# Zuino_M_UNO.net
KiCad netlist of a schematic drawn in EAGLE
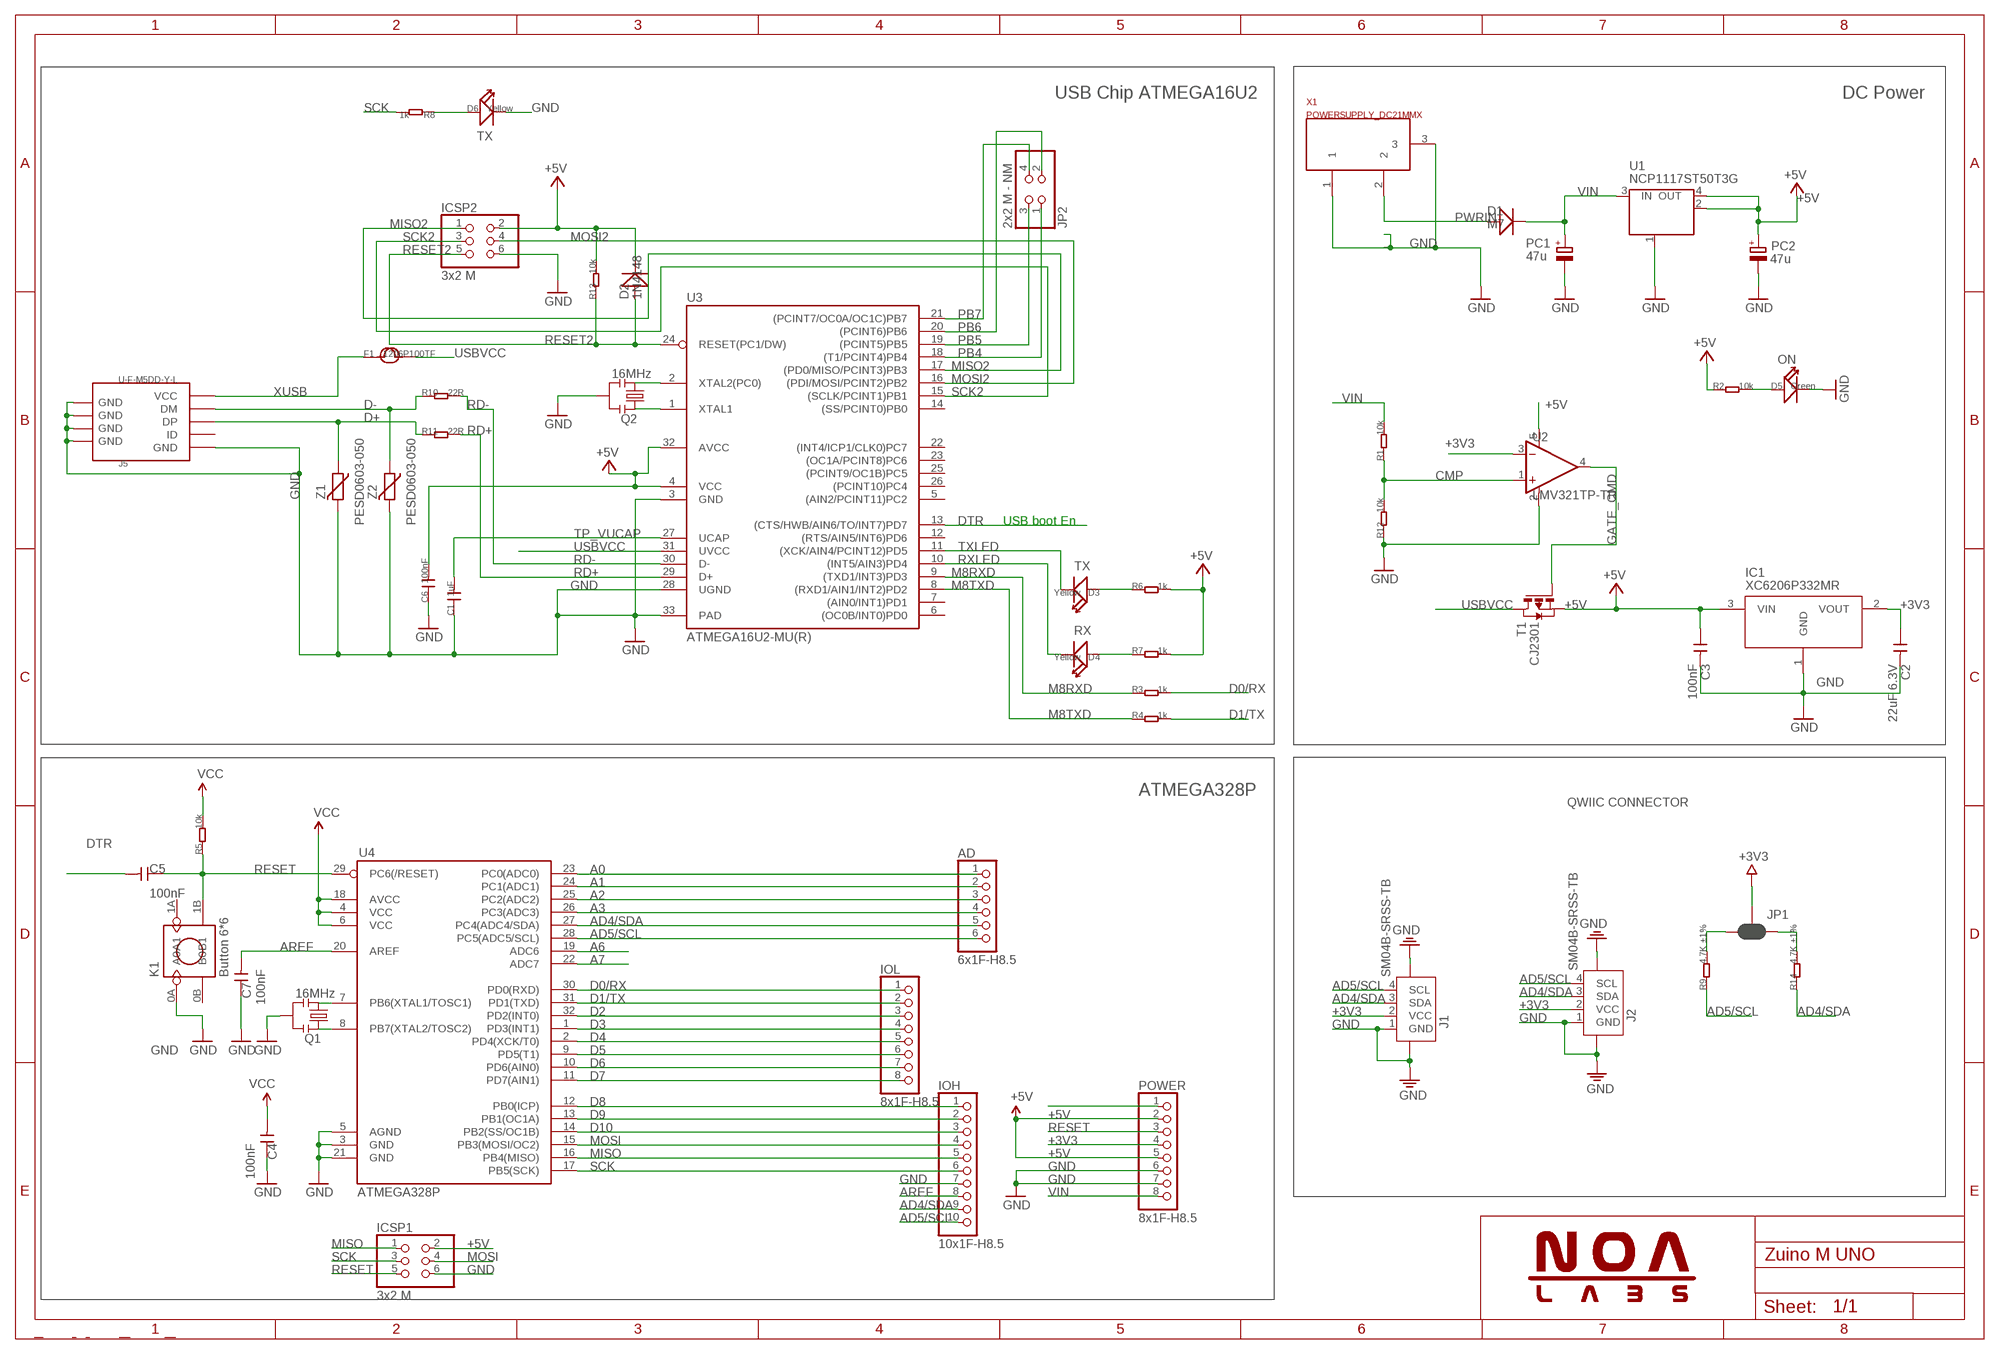
[diagram p0: schematic, sheet 1]

(export (version "E")
  (design (tool "Eeschema 10.0.6"))
  (components
    (comp (ref "AD")
      (value "6x1F-H8.5")
      (footprint "eagle-import:1X06")
      (libsource (lib "eagle-import") (part "PINHD-1X6"))
    )
    (comp (ref "C1")
      (value "1uF")
      (footprint "eagle-import:0603")
      (libsource (lib "eagle-import") (part "C-0603"))
    )
    (comp (ref "C2")
      (value "22uF 6.3V")
      (footprint "eagle-import:0603")
      (libsource (lib "eagle-import") (part "C-0603"))
    )
    (comp (ref "C3")
      (value "100nF")
      (footprint "eagle-import:0603")
      (libsource (lib "eagle-import") (part "C-0603"))
    )
    (comp (ref "C4")
      (value "100nF")
      (footprint "eagle-import:0603")
      (libsource (lib "eagle-import") (part "C-0603"))
    )
    (comp (ref "C5")
      (value "100nF")
      (footprint "eagle-import:0603")
      (libsource (lib "eagle-import") (part "C-0603"))
    )
    (comp (ref "C6")
      (value "100nF")
      (footprint "eagle-import:0603")
      (libsource (lib "eagle-import") (part "C-0603"))
    )
    (comp (ref "C7")
      (value "100nF")
      (footprint "eagle-import:0603")
      (libsource (lib "eagle-import") (part "C-0603"))
    )
    (comp (ref "D1")
      (value "M7")
      (footprint "eagle-import:SMA")
      (libsource (lib "eagle-import") (part "D-B130L-13-F"))
    )
    (comp (ref "D2")
      (value "1N4148")
      (footprint "eagle-import:SOD123")
      (libsource (lib "eagle-import") (part "D'1206'"))
    )
    (comp (ref "D3")
      (value "Yellow")
      (footprint "eagle-import:LED-0805")
      (libsource (lib "eagle-import") (part "LED'0805'"))
    )
    (comp (ref "D4")
      (value "Yellow")
      (footprint "eagle-import:LED-0805")
      (libsource (lib "eagle-import") (part "LED'0805'"))
    )
    (comp (ref "D5")
      (value "Green")
      (footprint "eagle-import:LED-0805")
      (libsource (lib "eagle-import") (part "LED'0805'"))
    )
    (comp (ref "D6")
      (value "Yellow")
      (footprint "eagle-import:LED-0805")
      (libsource (lib "eagle-import") (part "LED'0805'"))
    )
    (comp (ref "F1")
      (value "1206P100TF")
      (footprint "eagle-import:1206")
      (libsource (lib "eagle-import") (part "FUSE1206"))
    )
    (comp (ref "IC1")
      (value "XC6206P332MR")
      (footprint "eagle-import:SOT23")
      (libsource (lib "eagle-import") (part "XC6206MR"))
    )
    (comp (ref "ICSP1")
      (value "3x2 M")
      (footprint "eagle-import:2X03")
      (libsource (lib "eagle-import") (part "PINHD-2X3"))
    )
    (comp (ref "ICSP2")
      (value "3x2 M")
      (footprint "eagle-import:2X03")
      (libsource (lib "eagle-import") (part "PINHD-2X3"))
    )
    (comp (ref "IOH")
      (value "10x1F-H8.5")
      (footprint "eagle-import:1X10")
      (libsource (lib "eagle-import") (part "PINHD-1X10_ARD"))
    )
    (comp (ref "IOL")
      (value "8x1F-H8.5")
      (footprint "eagle-import:1X08")
      (libsource (lib "eagle-import") (part "PINHD-1X8"))
    )
    (comp (ref "J1")
      (value "SM04B-SRSS-TB")
      (footprint "eagle-import:JST-SH-4P")
      (libsource (lib "eagle-import") (part "JST-SH-4P-1.0"))
    )
    (comp (ref "J2")
      (value "SM04B-SRSS-TB")
      (footprint "eagle-import:JST-SH-4P")
      (libsource (lib "eagle-import") (part "JST-SH-4P-1.0"))
    )
    (comp (ref "J5")
      (value "U-F-M5DD-Y-L")
      (footprint "eagle-import:MICRO-SMD")
      (libsource (lib "eagle-import") (part "USB-MICROE"))
    )
    (comp (ref "JP1")
      (value "JUMPER-SMT_3_2-NC_PASTE_SILK")
      (footprint "eagle-import:SMT-JUMPER_3_2-NC_PASTE_SILK")
      (libsource (lib "eagle-import") (part "JUMPER-SMT_3_2-NC_PASTE_SILK"))
    )
    (comp (ref "JP2")
      (value "2x2 M - NM")
      (footprint "eagle-import:2X02")
      (libsource (lib "eagle-import") (part "PINHD-2X2"))
    )
    (comp (ref "K1")
      (value "Button 6*6")
      (footprint "eagle-import:4P-SMD-6X6")
      (libsource (lib "eagle-import") (part "BOTTON-4P-6X6"))
    )
    (comp (ref "PC1")
      (value "47u")
      (footprint "eagle-import:PANASONIC_D")
      (libsource (lib "eagle-import") (part "CPOL-EUD"))
    )
    (comp (ref "PC2")
      (value "47u")
      (footprint "eagle-import:PANASONIC_D")
      (libsource (lib "eagle-import") (part "CPOL-EUD"))
    )
    (comp (ref "POWER")
      (value "8x1F-H8.5")
      (footprint "eagle-import:1X08")
      (libsource (lib "eagle-import") (part "PINHD-1X8"))
    )
    (comp (ref "Q1")
      (value "16MHz")
      (footprint "eagle-import:RESONATOR-SMD")
      (libsource (lib "eagle-import") (part "RESONATORSMD"))
    )
    (comp (ref "Q2")
      (value "16MHz")
      (footprint "eagle-import:RESONATOR-SMD")
      (libsource (lib "eagle-import") (part "RESONATORSMD"))
    )
    (comp (ref "R1")
      (value "10k")
      (footprint "eagle-import:0603")
      (libsource (lib "eagle-import") (part "R-0603"))
    )
    (comp (ref "R2")
      (value "10k")
      (footprint "eagle-import:0603")
      (libsource (lib "eagle-import") (part "R-0603"))
    )
    (comp (ref "R3")
      (value "1k")
      (footprint "eagle-import:0603")
      (libsource (lib "eagle-import") (part "R-0603"))
    )
    (comp (ref "R4")
      (value "1k")
      (footprint "eagle-import:0603")
      (libsource (lib "eagle-import") (part "R-0603"))
    )
    (comp (ref "R5")
      (value "10k")
      (footprint "eagle-import:0603")
      (libsource (lib "eagle-import") (part "R-0603"))
    )
    (comp (ref "R6")
      (value "1k")
      (footprint "eagle-import:0603")
      (libsource (lib "eagle-import") (part "R-0603"))
    )
    (comp (ref "R7")
      (value "1k")
      (footprint "eagle-import:0603")
      (libsource (lib "eagle-import") (part "R-0603"))
    )
    (comp (ref "R8")
      (value "1k")
      (footprint "eagle-import:0603")
      (libsource (lib "eagle-import") (part "R-0603"))
    )
    (comp (ref "R9")
      (value "4.7K ±1%")
      (footprint "eagle-import:0603")
      (libsource (lib "eagle-import") (part "Discretex_R-0603"))
    )
    (comp (ref "R10")
      (value "22R")
      (footprint "eagle-import:0603")
      (libsource (lib "eagle-import") (part "R-0603"))
    )
    (comp (ref "R11")
      (value "22R")
      (footprint "eagle-import:0603")
      (libsource (lib "eagle-import") (part "R-0603"))
    )
    (comp (ref "R12")
      (value "10k")
      (footprint "eagle-import:0603")
      (libsource (lib "eagle-import") (part "R-0603"))
    )
    (comp (ref "R13")
      (value "10k")
      (footprint "eagle-import:0603")
      (libsource (lib "eagle-import") (part "R-0603"))
    )
    (comp (ref "R14")
      (value "4.7K ±1%")
      (footprint "eagle-import:0603")
      (libsource (lib "eagle-import") (part "Discretex_R-0603"))
    )
    (comp (ref "T1")
      (value "CJ2301")
      (footprint "eagle-import:SOT-23")
      (libsource (lib "eagle-import") (part "PMOSSOT23"))
    )
    (comp (ref "U1")
      (value "NCP1117ST50T3G")
      (footprint "eagle-import:SOT223")
      (libsource (lib "eagle-import") (part "MC33269ST-3.3T3"))
    )
    (comp (ref "U2")
      (value "LMV321TP-TR")
      (footprint "eagle-import:SOT23-5")
      (libsource (lib "eagle-import") (part "LM321"))
    )
    (comp (ref "U3")
      (value "ATMEGA16U2-MU(R)")
      (footprint "eagle-import:MLF32")
      (libsource (lib "eagle-import") (part "ATMEGA16U2-MU"))
    )
    (comp (ref "U4")
      (value "ATMEGA328P")
      (footprint "eagle-import:TQFP32-08")
      (libsource (lib "eagle-import") (part "ATMEGA168"))
    )
    (comp (ref "X1")
      (value "POWERSUPPLY_DC21MMX")
      (footprint "eagle-import:POWERSUPPLY_DC-21MM")
      (libsource (lib "eagle-import") (part "POWERSUPPLY_DC21MMX"))
    )
    (comp (ref "Z1")
      (value "PESD0603-050")
      (footprint "eagle-import:CT_CN0603")
      (libsource (lib "eagle-import") (part "VARISTORCN0603"))
    )
    (comp (ref "Z2")
      (value "PESD0603-050")
      (footprint "eagle-import:CT_CN0603")
      (libsource (lib "eagle-import") (part "VARISTORCN0603"))
    )
  )
  (nets
    (net (code "1") (name "+3V3") (class "Default")
      (node (ref "C2") (pin "1") (pinfunction "1_1") (pintype "passive"))
      (node (ref "IC1") (pin "2") (pinfunction "VOUT_2") (pintype "bidirectional"))
      (node (ref "J1") (pin "2") (pinfunction "VCC_2") (pintype "bidirectional"))
      (node (ref "J2") (pin "2") (pinfunction "VCC_2") (pintype "bidirectional"))
      (node (ref "JP1") (pin "2") (pinfunction "2_2") (pintype "passive"))
      (node (ref "POWER") (pin "4") (pinfunction "4_4") (pintype "passive"))
      (node (ref "U2") (pin "3") (pinfunction "IN-_3") (pintype "input"))
    )
    (net (code "2") (name "+5V") (class "Default")
      (node (ref "C3") (pin "1") (pinfunction "1_1") (pintype "passive"))
      (node (ref "C4") (pin "2") (pinfunction "2_2") (pintype "passive"))
      (node (ref "C6") (pin "2") (pinfunction "2_2") (pintype "passive"))
      (node (ref "D2") (pin "-") (pinfunction "-_-") (pintype "passive"))
      (node (ref "IC1") (pin "3") (pinfunction "VIN_3") (pintype "bidirectional"))
      (node (ref "ICSP1") (pin "2") (pinfunction "2_2") (pintype "passive"))
      (node (ref "ICSP2") (pin "2") (pinfunction "2_2") (pintype "passive"))
      (node (ref "PC2") (pin "+") (pinfunction "+_+") (pintype "passive"))
      (node (ref "POWER") (pin "2") (pinfunction "2_2") (pintype "passive"))
      (node (ref "POWER") (pin "5") (pinfunction "5_5") (pintype "passive"))
      (node (ref "R13") (pin "2") (pinfunction "2_2") (pintype "passive"))
      (node (ref "R2") (pin "1") (pinfunction "1_1") (pintype "passive"))
      (node (ref "R5") (pin "2") (pinfunction "2_2") (pintype "passive"))
      (node (ref "R6") (pin "2") (pinfunction "2_2") (pintype "passive"))
      (node (ref "R7") (pin "2") (pinfunction "2_2") (pintype "passive"))
      (node (ref "T1") (pin "2") (pinfunction "S_2") (pintype "passive"))
      (node (ref "U1") (pin "2") (pinfunction "OUT_2") (pintype "passive"))
      (node (ref "U1") (pin "4") (pinfunction "OUT_4") (pintype "passive"))
      (node (ref "U2") (pin "5") (pinfunction "V+_5") (pintype "power_in"))
      (node (ref "U3") (pin "32") (pinfunction "AVCC_32") (pintype "power_in"))
      (node (ref "U3") (pin "4") (pinfunction "VCC_4") (pintype "power_in"))
      (node (ref "U4") (pin "18") (pinfunction "AVCC_18") (pintype "bidirectional"))
      (node (ref "U4") (pin "4") (pinfunction "VCC_4") (pintype "bidirectional"))
      (node (ref "U4") (pin "6") (pinfunction "VCC_6") (pintype "bidirectional"))
    )
    (net (code "3") (name "/A0") (class "Default")
      (node (ref "AD") (pin "1") (pinfunction "1_1") (pintype "passive"))
      (node (ref "U4") (pin "23") (pinfunction "PC0(ADC0)_23") (pintype "bidirectional"))
    )
    (net (code "4") (name "/A1") (class "Default")
      (node (ref "AD") (pin "2") (pinfunction "2_2") (pintype "passive"))
      (node (ref "U4") (pin "24") (pinfunction "PC1(ADC1)_24") (pintype "bidirectional"))
    )
    (net (code "5") (name "/A2") (class "Default")
      (node (ref "AD") (pin "3") (pinfunction "3_3") (pintype "passive"))
      (node (ref "U4") (pin "25") (pinfunction "PC2(ADC2)_25") (pintype "bidirectional"))
    )
    (net (code "6") (name "/A3") (class "Default")
      (node (ref "AD") (pin "4") (pinfunction "4_4") (pintype "passive"))
      (node (ref "U4") (pin "26") (pinfunction "PC3(ADC3)_26") (pintype "bidirectional"))
    )
    (net (code "7") (name "/A6") (class "Default")
      (node (ref "U4") (pin "19") (pinfunction "ADC6_19") (pintype "bidirectional"))
    )
    (net (code "8") (name "/A7") (class "Default")
      (node (ref "U4") (pin "22") (pinfunction "ADC7_22") (pintype "bidirectional"))
    )
    (net (code "9") (name "/AD4{slash}SDA") (class "Default")
      (node (ref "AD") (pin "5") (pinfunction "5_5") (pintype "passive"))
      (node (ref "IOH") (pin "9") (pinfunction "9_9") (pintype "passive"))
      (node (ref "J1") (pin "3") (pinfunction "SDA_3") (pintype "bidirectional"))
      (node (ref "J2") (pin "3") (pinfunction "SDA_3") (pintype "bidirectional"))
      (node (ref "R14") (pin "1") (pinfunction "1_1") (pintype "passive"))
      (node (ref "U4") (pin "27") (pinfunction "PC4(ADC4/SDA)_27") (pintype "bidirectional"))
    )
    (net (code "10") (name "/AD5{slash}SCL") (class "Default")
      (node (ref "AD") (pin "6") (pinfunction "6_6") (pintype "passive"))
      (node (ref "IOH") (pin "10") (pinfunction "10_10") (pintype "passive"))
      (node (ref "J1") (pin "4") (pinfunction "SCL_4") (pintype "bidirectional"))
      (node (ref "J2") (pin "4") (pinfunction "SCL_4") (pintype "bidirectional"))
      (node (ref "R9") (pin "1") (pinfunction "1_1") (pintype "passive"))
      (node (ref "U4") (pin "28") (pinfunction "PC5(ADC5/SCL)_28") (pintype "bidirectional"))
    )
    (net (code "11") (name "/AREF") (class "Default")
      (node (ref "C7") (pin "2") (pinfunction "2_2") (pintype "passive"))
      (node (ref "IOH") (pin "8") (pinfunction "8_8") (pintype "passive"))
      (node (ref "U4") (pin "20") (pinfunction "AREF_20") (pintype "bidirectional"))
    )
    (net (code "12") (name "/CMP") (class "Default")
      (node (ref "R1") (pin "1") (pinfunction "1_1") (pintype "passive"))
      (node (ref "R12") (pin "2") (pinfunction "2_2") (pintype "passive"))
      (node (ref "U2") (pin "1") (pinfunction "IN+_1") (pintype "input"))
    )
    (net (code "13") (name "/D+") (class "Default")
      (node (ref "J5") (pin "D+") (pinfunction "DP_D+") (pintype "bidirectional"))
      (node (ref "R11") (pin "1") (pinfunction "1_1") (pintype "passive"))
      (node (ref "Z1") (pin "1") (pinfunction "1_1") (pintype "passive"))
    )
    (net (code "14") (name "/D-") (class "Default")
      (node (ref "J5") (pin "D-") (pinfunction "DM_D-") (pintype "bidirectional"))
      (node (ref "R10") (pin "1") (pinfunction "1_1") (pintype "passive"))
      (node (ref "Z2") (pin "1") (pinfunction "1_1") (pintype "passive"))
    )
    (net (code "15") (name "/D0{slash}RX") (class "Default")
      (node (ref "IOL") (pin "1") (pinfunction "1_1") (pintype "passive"))
      (node (ref "R3") (pin "2") (pinfunction "2_2") (pintype "passive"))
      (node (ref "U4") (pin "30") (pinfunction "PD0(RXD)_30") (pintype "bidirectional"))
    )
    (net (code "16") (name "/D1{slash}TX") (class "Default")
      (node (ref "IOL") (pin "2") (pinfunction "2_2") (pintype "passive"))
      (node (ref "R4") (pin "2") (pinfunction "2_2") (pintype "passive"))
      (node (ref "U4") (pin "31") (pinfunction "PD1(TXD)_31") (pintype "bidirectional"))
    )
    (net (code "17") (name "/D2") (class "Default")
      (node (ref "IOL") (pin "3") (pinfunction "3_3") (pintype "passive"))
      (node (ref "U4") (pin "32") (pinfunction "PD2(INT0)_32") (pintype "bidirectional"))
    )
    (net (code "18") (name "/D3") (class "Default")
      (node (ref "IOL") (pin "4") (pinfunction "4_4") (pintype "passive"))
      (node (ref "U4") (pin "1") (pinfunction "PD3(INT1)_1") (pintype "bidirectional"))
    )
    (net (code "19") (name "/D4") (class "Default")
      (node (ref "IOL") (pin "5") (pinfunction "5_5") (pintype "passive"))
      (node (ref "U4") (pin "2") (pinfunction "PD4(XCK/T0)_2") (pintype "bidirectional"))
    )
    (net (code "20") (name "/D5") (class "Default")
      (node (ref "IOL") (pin "6") (pinfunction "6_6") (pintype "passive"))
      (node (ref "U4") (pin "9") (pinfunction "PD5(T1)_9") (pintype "bidirectional"))
    )
    (net (code "21") (name "/D6") (class "Default")
      (node (ref "IOL") (pin "7") (pinfunction "7_7") (pintype "passive"))
      (node (ref "U4") (pin "10") (pinfunction "PD6(AIN0)_10") (pintype "bidirectional"))
    )
    (net (code "22") (name "/D7") (class "Default")
      (node (ref "IOL") (pin "8") (pinfunction "8_8") (pintype "passive"))
      (node (ref "U4") (pin "11") (pinfunction "PD7(AIN1)_11") (pintype "bidirectional"))
    )
    (net (code "23") (name "/D8") (class "Default")
      (node (ref "IOH") (pin "1") (pinfunction "1_1") (pintype "passive"))
      (node (ref "U4") (pin "12") (pinfunction "PB0(ICP)_12") (pintype "bidirectional"))
    )
    (net (code "24") (name "/D9") (class "Default")
      (node (ref "IOH") (pin "2") (pinfunction "2_2") (pintype "passive"))
      (node (ref "U4") (pin "13") (pinfunction "PB1(OC1A)_13") (pintype "bidirectional"))
    )
    (net (code "25") (name "/D10") (class "Default")
      (node (ref "IOH") (pin "3") (pinfunction "3_3") (pintype "passive"))
      (node (ref "U4") (pin "14") (pinfunction "PB2(SS/OC1B)_14") (pintype "bidirectional"))
    )
    (net (code "26") (name "/DTR") (class "Default")
      (node (ref "C5") (pin "2") (pinfunction "2_2") (pintype "passive"))
      (node (ref "U3") (pin "13") (pinfunction "(CTS/HWB/AIN6/TO/INT7)PD7_13") (pintype "bidirectional"))
    )
    (net (code "27") (name "/GATE_CMD") (class "Default")
      (node (ref "T1") (pin "3") (pinfunction "G_3") (pintype "passive"))
      (node (ref "U2") (pin "4") (pinfunction "OUT_4") (pintype "output"))
    )
    (net (code "28") (name "/M8RXD") (class "Default")
      (node (ref "R3") (pin "1") (pinfunction "1_1") (pintype "passive"))
      (node (ref "U3") (pin "9") (pinfunction "(TXD1/INT3)PD3_9") (pintype "bidirectional"))
    )
    (net (code "29") (name "/M8TXD") (class "Default")
      (node (ref "R4") (pin "1") (pinfunction "1_1") (pintype "passive"))
      (node (ref "U3") (pin "8") (pinfunction "(RXD1/AIN1/INT2)PD2_8") (pintype "bidirectional"))
    )
    (net (code "30") (name "/MISO") (class "Default")
      (node (ref "ICSP1") (pin "1") (pinfunction "1_1") (pintype "passive"))
      (node (ref "IOH") (pin "5") (pinfunction "5_5") (pintype "passive"))
      (node (ref "U4") (pin "16") (pinfunction "PB4(MISO)_16") (pintype "bidirectional"))
    )
    (net (code "31") (name "/MISO2") (class "Default")
      (node (ref "ICSP2") (pin "1") (pinfunction "1_1") (pintype "passive"))
      (node (ref "U3") (pin "17") (pinfunction "(PD0/MISO/PCINT3)PB3_17") (pintype "bidirectional"))
    )
    (net (code "32") (name "/MOSI") (class "Default")
      (node (ref "ICSP1") (pin "4") (pinfunction "4_4") (pintype "passive"))
      (node (ref "IOH") (pin "4") (pinfunction "4_4") (pintype "passive"))
      (node (ref "U4") (pin "15") (pinfunction "PB3(MOSI/OC2)_15") (pintype "bidirectional"))
    )
    (net (code "33") (name "/MOSI2") (class "Default")
      (node (ref "ICSP2") (pin "4") (pinfunction "4_4") (pintype "passive"))
      (node (ref "U3") (pin "16") (pinfunction "(PDI/MOSI/PCINT2)PB2_16") (pintype "bidirectional"))
    )
    (net (code "34") (name "/PB4") (class "Default")
      (node (ref "JP2") (pin "1") (pinfunction "1_1") (pintype "passive"))
      (node (ref "U3") (pin "18") (pinfunction "(T1/PCINT4)PB4_18") (pintype "bidirectional"))
    )
    (net (code "35") (name "/PB5") (class "Default")
      (node (ref "JP2") (pin "3") (pinfunction "3_3") (pintype "passive"))
      (node (ref "U3") (pin "19") (pinfunction "(PCINT5)PB5_19") (pintype "bidirectional"))
    )
    (net (code "36") (name "/PB6") (class "Default")
      (node (ref "JP2") (pin "2") (pinfunction "2_2") (pintype "passive"))
      (node (ref "U3") (pin "20") (pinfunction "(PCINT6)PB6_20") (pintype "bidirectional"))
    )
    (net (code "37") (name "/PB7") (class "Default")
      (node (ref "JP2") (pin "4") (pinfunction "4_4") (pintype "passive"))
      (node (ref "U3") (pin "21") (pinfunction "(PCINT7/OC0A/OC1C)PB7_21") (pintype "bidirectional"))
    )
    (net (code "38") (name "/PWRIN") (class "Default")
      (node (ref "D1") (pin "P$2") (pinfunction "+_P$2") (pintype "passive"))
      (node (ref "X1") (pin "2") (pinfunction "2_2") (pintype "power_in"))
    )
    (net (code "39") (name "/RD+") (class "Default")
      (node (ref "R11") (pin "2") (pinfunction "2_2") (pintype "passive"))
      (node (ref "U3") (pin "29") (pinfunction "D+_29") (pintype "bidirectional"))
    )
    (net (code "40") (name "/RD-") (class "Default")
      (node (ref "R10") (pin "2") (pinfunction "2_2") (pintype "passive"))
      (node (ref "U3") (pin "30") (pinfunction "D-_30") (pintype "bidirectional"))
    )
    (net (code "41") (name "/RESET") (class "Default")
      (node (ref "C5") (pin "1") (pinfunction "1_1") (pintype "passive"))
      (node (ref "ICSP1") (pin "5") (pinfunction "5_5") (pintype "passive"))
      (node (ref "K1") (pin "1B") (pinfunction "B1_1B") (pintype "bidirectional"))
      (node (ref "POWER") (pin "3") (pinfunction "3_3") (pintype "passive"))
      (node (ref "R5") (pin "1") (pinfunction "1_1") (pintype "passive"))
      (node (ref "U4") (pin "29") (pinfunction "PC6(/RESET)_29") (pintype "bidirectional"))
    )
    (net (code "42") (name "/RESET2") (class "Default")
      (node (ref "D2") (pin "+") (pinfunction "+_+") (pintype "passive"))
      (node (ref "ICSP2") (pin "5") (pinfunction "5_5") (pintype "passive"))
      (node (ref "R13") (pin "1") (pinfunction "1_1") (pintype "passive"))
      (node (ref "U3") (pin "24") (pinfunction "RESET(PC1/DW)_24") (pintype "input"))
    )
    (net (code "43") (name "/RXLED") (class "Default")
      (node (ref "D4") (pin "-") (pinfunction "-_-") (pintype "passive"))
      (node (ref "U3") (pin "10") (pinfunction "(INT5/AIN3)PD4_10") (pintype "bidirectional"))
    )
    (net (code "44") (name "/SCK") (class "Default")
      (node (ref "ICSP1") (pin "3") (pinfunction "3_3") (pintype "passive"))
      (node (ref "IOH") (pin "6") (pinfunction "6_6") (pintype "passive"))
      (node (ref "R8") (pin "2") (pinfunction "2_2") (pintype "passive"))
      (node (ref "U4") (pin "17") (pinfunction "PB5(SCK)_17") (pintype "bidirectional"))
    )
    (net (code "45") (name "/SCK2") (class "Default")
      (node (ref "ICSP2") (pin "3") (pinfunction "3_3") (pintype "passive"))
      (node (ref "U3") (pin "15") (pinfunction "(SCLK/PCINT1)PB1_15") (pintype "bidirectional"))
    )
    (net (code "46") (name "/TP_VUCAP") (class "Default")
      (node (ref "C1") (pin "2") (pinfunction "2_2") (pintype "passive"))
      (node (ref "U3") (pin "27") (pinfunction "UCAP_27") (pintype "passive"))
    )
    (net (code "47") (name "/TXLED") (class "Default")
      (node (ref "D3") (pin "-") (pinfunction "-_-") (pintype "passive"))
      (node (ref "U3") (pin "11") (pinfunction "(XCK/AIN4/PCINT12)PD5_11") (pintype "bidirectional"))
    )
    (net (code "48") (name "/USBVCC") (class "Default")
      (node (ref "F1") (pin "2") (pinfunction "2_2") (pintype "bidirectional"))
      (node (ref "T1") (pin "1") (pinfunction "D_1") (pintype "passive"))
      (node (ref "U3") (pin "31") (pinfunction "UVCC_31") (pintype "power_in"))
    )
    (net (code "49") (name "/VIN") (class "Default")
      (node (ref "D1") (pin "P$1") (pinfunction "-_P$1") (pintype "passive"))
      (node (ref "PC1") (pin "+") (pinfunction "+_+") (pintype "passive"))
      (node (ref "POWER") (pin "8") (pinfunction "8_8") (pintype "passive"))
      (node (ref "R1") (pin "2") (pinfunction "2_2") (pintype "passive"))
      (node (ref "U1") (pin "3") (pinfunction "IN_3") (pintype "input"))
    )
    (net (code "50") (name "/XUSB") (class "Default")
      (node (ref "F1") (pin "1") (pinfunction "1_1") (pintype "bidirectional"))
      (node (ref "J5") (pin "VBUS") (pinfunction "VCC_VBUS") (pintype "bidirectional"))
    )
    (net (code "51") (name "GND") (class "Default")
      (node (ref "C1") (pin "1") (pinfunction "1_1") (pintype "passive"))
      (node (ref "C2") (pin "2") (pinfunction "2_2") (pintype "passive"))
      (node (ref "C3") (pin "2") (pinfunction "2_2") (pintype "passive"))
      (node (ref "C4") (pin "1") (pinfunction "1_1") (pintype "passive"))
      (node (ref "C6") (pin "1") (pinfunction "1_1") (pintype "passive"))
      (node (ref "C7") (pin "1") (pinfunction "1_1") (pintype "passive"))
      (node (ref "D5") (pin "-") (pinfunction "-_-") (pintype "passive"))
      (node (ref "D6") (pin "-") (pinfunction "-_-") (pintype "passive"))
      (node (ref "IC1") (pin "1") (pinfunction "GND_1") (pintype "bidirectional"))
      (node (ref "ICSP1") (pin "6") (pinfunction "6_6") (pintype "passive"))
      (node (ref "ICSP2") (pin "6") (pinfunction "6_6") (pintype "passive"))
      (node (ref "IOH") (pin "7") (pinfunction "7_7") (pintype "passive"))
      (node (ref "J1") (pin "1") (pinfunction "GND_1") (pintype "bidirectional"))
      (node (ref "J1") (pin "NC1") (pinfunction "5_NC1") (pintype "bidirectional"))
      (node (ref "J1") (pin "NC2") (pinfunction "6_NC2") (pintype "bidirectional"))
      (node (ref "J2") (pin "1") (pinfunction "GND_1") (pintype "bidirectional"))
      (node (ref "J2") (pin "NC1") (pinfunction "5_NC1") (pintype "bidirectional"))
      (node (ref "J2") (pin "NC2") (pinfunction "6_NC2") (pintype "bidirectional"))
      (node (ref "J5") (pin "GND") (pinfunction "GND_GND") (pintype "bidirectional"))
      (node (ref "J5") (pin "S1") (pinfunction "GND_S1") (pintype "bidirectional"))
      (node (ref "J5") (pin "S1@1") (pinfunction "GND_S1@1") (pintype "bidirectional"))
      (node (ref "J5") (pin "S1@2") (pinfunction "GND_S1@2") (pintype "bidirectional"))
      (node (ref "J5") (pin "S2") (pinfunction "GND_S2") (pintype "bidirectional"))
      (node (ref "J5") (pin "S2@1") (pinfunction "GND_S2@1") (pintype "bidirectional"))
      (node (ref "J5") (pin "S2@2") (pinfunction "GND_S2@2") (pintype "bidirectional"))
      (node (ref "J5") (pin "S3") (pinfunction "GND_S3") (pintype "bidirectional"))
      (node (ref "J5") (pin "S3@1") (pinfunction "GND_S3@1") (pintype "bidirectional"))
      (node (ref "J5") (pin "S3@2") (pinfunction "GND_S3@2") (pintype "bidirectional"))
      (node (ref "J5") (pin "S4") (pinfunction "GND_S4") (pintype "bidirectional"))
      (node (ref "J5") (pin "S4@1") (pinfunction "GND_S4@1") (pintype "bidirectional"))
      (node (ref "J5") (pin "S4@2") (pinfunction "GND_S4@2") (pintype "bidirectional"))
      (node (ref "K1") (pin "0A") (pinfunction "A0_0A") (pintype "bidirectional"))
      (node (ref "PC1") (pin "-") (pinfunction "-_-") (pintype "passive"))
      (node (ref "PC2") (pin "-") (pinfunction "-_-") (pintype "passive"))
      (node (ref "POWER") (pin "6") (pinfunction "6_6") (pintype "passive"))
      (node (ref "POWER") (pin "7") (pinfunction "7_7") (pintype "passive"))
      (node (ref "Q1") (pin "2") (pinfunction "2_2") (pintype "passive"))
      (node (ref "Q2") (pin "2") (pinfunction "2_2") (pintype "passive"))
      (node (ref "R12") (pin "1") (pinfunction "1_1") (pintype "passive"))
      (node (ref "U1") (pin "1") (pinfunction "GND/ADJ_1") (pintype "input"))
      (node (ref "U2") (pin "2") (pinfunction "V-_2") (pintype "power_in"))
      (node (ref "U3") (pin "28") (pinfunction "UGND_28") (pintype "power_in"))
      (node (ref "U3") (pin "3") (pinfunction "GND_3") (pintype "power_in"))
      (node (ref "U3") (pin "33") (pinfunction "PAD_33") (pintype "power_in"))
      (node (ref "U4") (pin "21") (pinfunction "GND_21") (pintype "bidirectional"))
      (node (ref "U4") (pin "3") (pinfunction "GND_3") (pintype "bidirectional"))
      (node (ref "U4") (pin "5") (pinfunction "AGND_5") (pintype "bidirectional"))
      (node (ref "X1") (pin "1") (pinfunction "1_1") (pintype "power_in"))
      (node (ref "X1") (pin "3") (pinfunction "3_3") (pintype "power_in"))
      (node (ref "Z1") (pin "2") (pinfunction "2_2") (pintype "passive"))
      (node (ref "Z2") (pin "2") (pinfunction "2_2") (pintype "passive"))
    )
    (net (code "52") (name "Net-(D3-Pad+)") (class "Default")
      (node (ref "D3") (pin "+") (pinfunction "+_+") (pintype "passive"))
      (node (ref "R6") (pin "1") (pinfunction "1_1") (pintype "passive"))
    )
    (net (code "53") (name "Net-(D4-Pad+)") (class "Default")
      (node (ref "D4") (pin "+") (pinfunction "+_+") (pintype "passive"))
      (node (ref "R7") (pin "1") (pinfunction "1_1") (pintype "passive"))
    )
    (net (code "54") (name "Net-(D5-Pad+)") (class "Default")
      (node (ref "D5") (pin "+") (pinfunction "+_+") (pintype "passive"))
      (node (ref "R2") (pin "2") (pinfunction "2_2") (pintype "passive"))
    )
    (net (code "55") (name "Net-(D6-Pad+)") (class "Default")
      (node (ref "D6") (pin "+") (pinfunction "+_+") (pintype "passive"))
      (node (ref "R8") (pin "1") (pinfunction "1_1") (pintype "passive"))
    )
    (net (code "56") (name "Net-(JP1-Pad1)") (class "Default")
      (node (ref "JP1") (pin "1") (pinfunction "1_1") (pintype "passive"))
      (node (ref "R14") (pin "2") (pinfunction "2_2") (pintype "passive"))
    )
    (net (code "57") (name "Net-(JP1-Pad3)") (class "Default")
      (node (ref "JP1") (pin "3") (pinfunction "3_3") (pintype "passive"))
      (node (ref "R9") (pin "2") (pinfunction "2_2") (pintype "passive"))
    )
    (net (code "58") (name "Net-(U3-XTAL1)") (class "Default")
      (node (ref "Q2") (pin "1") (pinfunction "1_1") (pintype "passive"))
      (node (ref "U3") (pin "1") (pinfunction "XTAL1_1") (pintype "bidirectional"))
    )
    (net (code "59") (name "Net-(U3-XTAL2(PC0))") (class "Default")
      (node (ref "Q2") (pin "3") (pinfunction "3_3") (pintype "passive"))
      (node (ref "U3") (pin "2") (pinfunction "XTAL2(PC0)_2") (pintype "bidirectional"))
    )
    (net (code "60") (name "Net-(U4-PB6(XTAL1{slash}TOSC1))") (class "Default")
      (node (ref "Q1") (pin "3") (pinfunction "3_3") (pintype "passive"))
      (node (ref "U4") (pin "7") (pinfunction "PB6(XTAL1/TOSC1)_7") (pintype "bidirectional"))
    )
    (net (code "61") (name "Net-(U4-PB7(XTAL2{slash}TOSC2))") (class "Default")
      (node (ref "Q1") (pin "1") (pinfunction "1_1") (pintype "passive"))
      (node (ref "U4") (pin "8") (pinfunction "PB7(XTAL2/TOSC2)_8") (pintype "bidirectional"))
    )
    (net (code "62") (name "unconnected-(J5-PadID)") (class "Default")
      (node (ref "J5") (pin "ID") (pinfunction "ID_ID") (pintype "bidirectional"))
    )
    (net (code "63") (name "unconnected-(K1-A1-Pad1A)") (class "Default")
      (node (ref "K1") (pin "1A") (pinfunction "A1_1A") (pintype "bidirectional"))
    )
    (net (code "64") (name "unconnected-(K1-B0-Pad0B)") (class "Default")
      (node (ref "K1") (pin "0B") (pinfunction "B0_0B") (pintype "bidirectional"))
    )
    (net (code "65") (name "unconnected-(POWER-Pad1)") (class "Default")
      (node (ref "POWER") (pin "1") (pinfunction "1_1") (pintype "passive"))
    )
    (net (code "66") (name "unconnected-(U3-(AIN0{slash}INT1)PD1-Pad7)") (class "Default")
      (node (ref "U3") (pin "7") (pinfunction "(AIN0/INT1)PD1_7") (pintype "bidirectional"))
    )
    (net (code "67") (name "unconnected-(U3-(AIN2{slash}PCINT11)PC2-Pad5)") (class "Default")
      (node (ref "U3") (pin "5") (pinfunction "(AIN2/PCINT11)PC2_5") (pintype "bidirectional"))
    )
    (net (code "68") (name "unconnected-(U3-(INT4{slash}ICP1{slash}CLK0)PC7-Pad22)") (class "Default")
      (node (ref "U3") (pin "22") (pinfunction "(INT4/ICP1/CLK0)PC7_22") (pintype "bidirectional"))
    )
    (net (code "69") (name "unconnected-(U3-(OC0B{slash}INT0)PD0-Pad6)") (class "Default")
      (node (ref "U3") (pin "6") (pinfunction "(OC0B/INT0)PD0_6") (pintype "bidirectional"))
    )
    (net (code "70") (name "unconnected-(U3-(OC1A{slash}PCINT8)PC6-Pad23)") (class "Default")
      (node (ref "U3") (pin "23") (pinfunction "(OC1A/PCINT8)PC6_23") (pintype "bidirectional"))
    )
    (net (code "71") (name "unconnected-(U3-(PCINT9{slash}OC1B)PC5-Pad25)") (class "Default")
      (node (ref "U3") (pin "25") (pinfunction "(PCINT9/OC1B)PC5_25") (pintype "bidirectional"))
    )
    (net (code "72") (name "unconnected-(U3-(PCINT10)PC4-Pad26)") (class "Default")
      (node (ref "U3") (pin "26") (pinfunction "(PCINT10)PC4_26") (pintype "bidirectional"))
    )
    (net (code "73") (name "unconnected-(U3-(RTS{slash}AIN5{slash}INT6)PD6-Pad12)") (class "Default")
      (node (ref "U3") (pin "12") (pinfunction "(RTS/AIN5/INT6)PD6_12") (pintype "bidirectional"))
    )
    (net (code "74") (name "unconnected-(U3-(SS{slash}PCINT0)PB0-Pad14)") (class "Default")
      (node (ref "U3") (pin "14") (pinfunction "(SS/PCINT0)PB0_14") (pintype "bidirectional"))
    )
  )
)
